# TM1637_display.net
KiCad netlist of a schematic drawn in Altium Designer
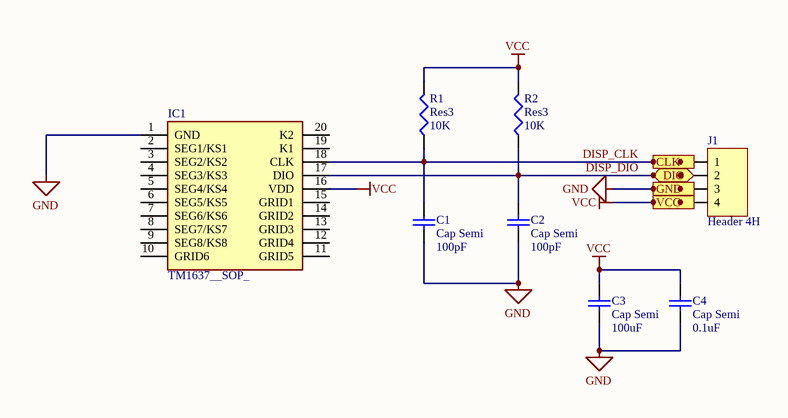
[diagram p0: TM1637_display.SchDoc]

(export (version "E")
  (design (tool "Eeschema 10.0.6"))
  (components
    (comp (ref "C1")
      (value "Cap Semi")
      (footprint "1608[0603]")
      (description "Capacitor (Semiconductor SIM Model)")
      (fields (field (name "ALTIUM_VALUE") "100pF") (field (name "PUBLISHER") "Altium Limited"))
      (libsource (lib "Miscellaneous Devices") (part "Cap Semi"))
    )
    (comp (ref "C2")
      (value "Cap Semi")
      (footprint "1608[0603]")
      (description "Capacitor (Semiconductor SIM Model)")
      (fields (field (name "ALTIUM_VALUE") "100pF") (field (name "PUBLISHER") "Altium Limited"))
      (libsource (lib "Miscellaneous Devices") (part "Cap Semi"))
    )
    (comp (ref "C3")
      (value "Cap Semi")
      (footprint "1608[0603]")
      (description "Capacitor (Semiconductor SIM Model)")
      (fields (field (name "ALTIUM_VALUE") "100uF") (field (name "PUBLISHER") "Altium Limited"))
      (libsource (lib "Miscellaneous Devices") (part "Cap Semi"))
    )
    (comp (ref "C4")
      (value "Cap Semi")
      (footprint "1608[0603]")
      (description "Capacitor (Semiconductor SIM Model)")
      (fields (field (name "ALTIUM_VALUE") "0.1uF") (field (name "PUBLISHER") "Altium Limited"))
      (libsource (lib "Miscellaneous Devices") (part "Cap Semi"))
    )
    (comp (ref "IC1")
      (value "TM1637__SOP_")
      (footprint "SamacSys:SOIC127P1045X280-20N")
      (description "Integrated Circuit")
      (fields (field (name "MANUFACTURER_PART_NUMBER") "TM1637 (SOP)"))
      (libsource (lib "*") (part "TM1637__SOP_"))
    )
    (comp (ref "J1")
      (value "Header 4H")
      (footprint "HDR1X4H")
      (description "Header, 4-Pin, Right Angle")
      (fields (field (name "PUBLISHER") "Altium Limited"))
      (libsource (lib "Miscellaneous Connectors") (part "Header 4H"))
    )
    (comp (ref "R1")
      (value "Res3")
      (footprint "J1-0603")
      (description "Resistor")
      (fields (field (name "ALTIUM_VALUE") "10K") (field (name "PUBLISHER") "Altium Limited"))
      (libsource (lib "Miscellaneous Devices") (part "Res3"))
    )
    (comp (ref "R2")
      (value "Res3")
      (footprint "J1-0603")
      (description "Resistor")
      (fields (field (name "ALTIUM_VALUE") "10K") (field (name "PUBLISHER") "Altium Limited"))
      (libsource (lib "Miscellaneous Devices") (part "Res3"))
    )
  )
  (nets
    (net (code "1") (name "/DISP_CLK") (class "Default")
      (node (ref "C1") (pin "2") (pinfunction "2_2") (pintype "passive"))
      (node (ref "IC1") (pin "18") (pinfunction "CLK_18") (pintype "passive"))
      (node (ref "J1") (pin "1") (pinfunction "1_1") (pintype "passive"))
      (node (ref "R1") (pin "1") (pinfunction "1_1") (pintype "passive"))
    )
    (net (code "2") (name "/DISP_DIO") (class "Default")
      (node (ref "C2") (pin "2") (pinfunction "2_2") (pintype "passive"))
      (node (ref "IC1") (pin "17") (pinfunction "DIO_17") (pintype "passive"))
      (node (ref "J1") (pin "2") (pinfunction "2_2") (pintype "passive"))
      (node (ref "R2") (pin "1") (pinfunction "1_1") (pintype "passive"))
    )
    (net (code "3") (name "GND") (class "Default")
      (node (ref "C1") (pin "1") (pinfunction "1_1") (pintype "passive"))
      (node (ref "C2") (pin "1") (pinfunction "1_1") (pintype "passive"))
      (node (ref "C3") (pin "1") (pinfunction "1_1") (pintype "passive"))
      (node (ref "C4") (pin "1") (pinfunction "1_1") (pintype "passive"))
      (node (ref "IC1") (pin "1") (pinfunction "GND_1") (pintype "passive"))
      (node (ref "J1") (pin "3") (pinfunction "3_3") (pintype "passive"))
    )
    (net (code "4") (name "VCC") (class "Default")
      (node (ref "C3") (pin "2") (pinfunction "2_2") (pintype "passive"))
      (node (ref "C4") (pin "2") (pinfunction "2_2") (pintype "passive"))
      (node (ref "IC1") (pin "16") (pinfunction "VDD_16") (pintype "passive"))
      (node (ref "J1") (pin "4") (pinfunction "4_4") (pintype "passive"))
      (node (ref "R1") (pin "2") (pinfunction "2_2") (pintype "passive"))
      (node (ref "R2") (pin "2") (pinfunction "2_2") (pintype "passive"))
    )
    (net (code "5") (name "unconnected-(IC1-GRID1-Pad15)") (class "Default")
      (node (ref "IC1") (pin "15") (pinfunction "GRID1_15") (pintype "passive"))
    )
    (net (code "6") (name "unconnected-(IC1-GRID2-Pad14)") (class "Default")
      (node (ref "IC1") (pin "14") (pinfunction "GRID2_14") (pintype "passive"))
    )
    (net (code "7") (name "unconnected-(IC1-GRID3-Pad13)") (class "Default")
      (node (ref "IC1") (pin "13") (pinfunction "GRID3_13") (pintype "passive"))
    )
    (net (code "8") (name "unconnected-(IC1-GRID4-Pad12)") (class "Default")
      (node (ref "IC1") (pin "12") (pinfunction "GRID4_12") (pintype "passive"))
    )
    (net (code "9") (name "unconnected-(IC1-GRID5-Pad11)") (class "Default")
      (node (ref "IC1") (pin "11") (pinfunction "GRID5_11") (pintype "passive"))
    )
    (net (code "10") (name "unconnected-(IC1-GRID6-Pad10)") (class "Default")
      (node (ref "IC1") (pin "10") (pinfunction "GRID6_10") (pintype "passive"))
    )
    (net (code "11") (name "unconnected-(IC1-K1-Pad19)") (class "Default")
      (node (ref "IC1") (pin "19") (pinfunction "K1_19") (pintype "passive"))
    )
    (net (code "12") (name "unconnected-(IC1-K2-Pad20)") (class "Default")
      (node (ref "IC1") (pin "20") (pinfunction "K2_20") (pintype "passive"))
    )
    (net (code "13") (name "unconnected-(IC1-SEG1{slash}KS1-Pad2)") (class "Default")
      (node (ref "IC1") (pin "2") (pinfunction "SEG1/KS1_2") (pintype "passive"))
    )
    (net (code "14") (name "unconnected-(IC1-SEG2{slash}KS2-Pad3)") (class "Default")
      (node (ref "IC1") (pin "3") (pinfunction "SEG2/KS2_3") (pintype "passive"))
    )
    (net (code "15") (name "unconnected-(IC1-SEG3{slash}KS3-Pad4)") (class "Default")
      (node (ref "IC1") (pin "4") (pinfunction "SEG3/KS3_4") (pintype "passive"))
    )
    (net (code "16") (name "unconnected-(IC1-SEG4{slash}KS4-Pad5)") (class "Default")
      (node (ref "IC1") (pin "5") (pinfunction "SEG4/KS4_5") (pintype "passive"))
    )
    (net (code "17") (name "unconnected-(IC1-SEG5{slash}KS5-Pad6)") (class "Default")
      (node (ref "IC1") (pin "6") (pinfunction "SEG5/KS5_6") (pintype "passive"))
    )
    (net (code "18") (name "unconnected-(IC1-SEG6{slash}KS6-Pad7)") (class "Default")
      (node (ref "IC1") (pin "7") (pinfunction "SEG6/KS6_7") (pintype "passive"))
    )
    (net (code "19") (name "unconnected-(IC1-SEG7{slash}KS7-Pad8)") (class "Default")
      (node (ref "IC1") (pin "8") (pinfunction "SEG7/KS7_8") (pintype "passive"))
    )
    (net (code "20") (name "unconnected-(IC1-SEG8{slash}KS8-Pad9)") (class "Default")
      (node (ref "IC1") (pin "9") (pinfunction "SEG8/KS8_9") (pintype "passive"))
    )
  )
)
